# MCU.net
KiCad netlist of a schematic drawn in Altium Designer
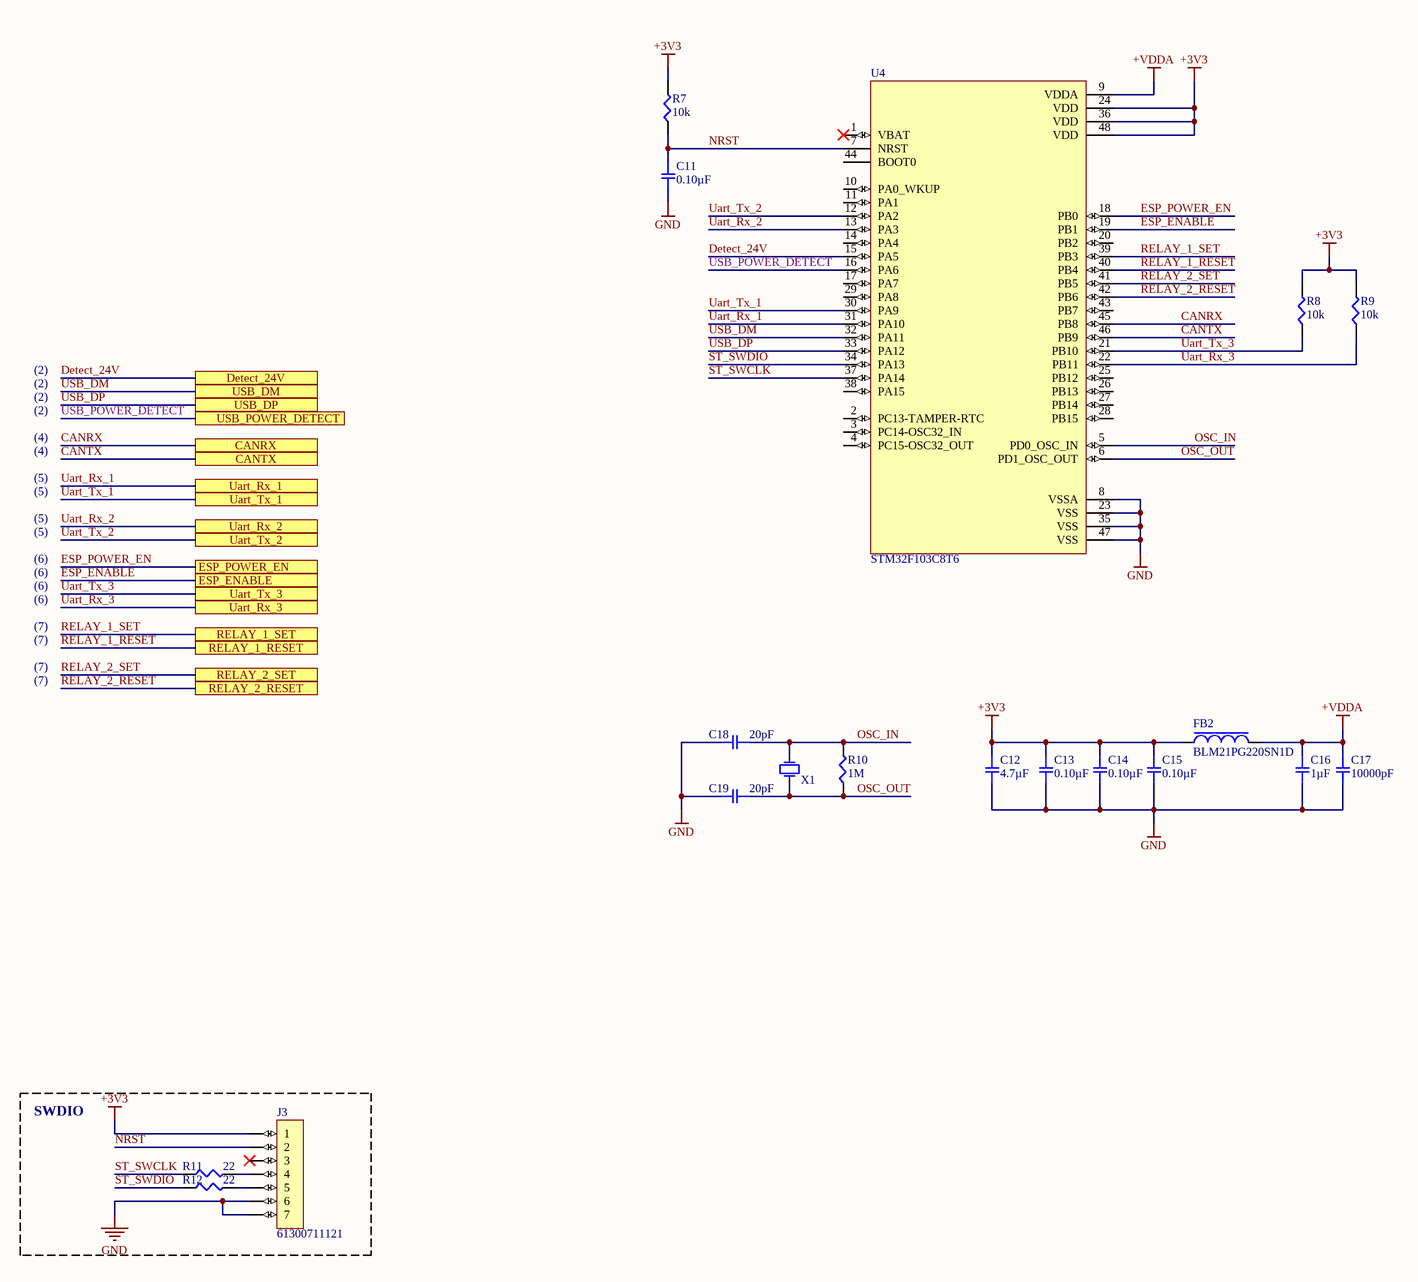
[diagram p0: MCU.SchDoc]

(export (version "E")
  (design (tool "Eeschema 10.0.6"))
  (components
    (comp (ref "C11")
      (value "0.10µF")
      (footprint "SMD-0603C")
      (description "CAP CER 0.1UF 50V X7R 0603")
      (fields
        (field (name "DIGI-KEY PART NUMBER") "490-5798-1-ND")
        (field (name "PART NUMBER") "GCJ188R71H104KA12D")
      )
      (libsource (lib "capacitor_murata_0603") (part "GCJ188R71H104KA12D"))
    )
    (comp (ref "C12")
      (value "4.7µF")
      (footprint "SMD-0805C")
      (description "CAP CER 4.7UF 16V X7R 0805")
      (fields
        (field (name "DIGI-KEY PART NUMBER") "490-10557-1-ND")
        (field (name "PART NUMBER") "GCJ21BR71C475KA01L")
      )
      (libsource (lib "capacitor_murata_0805") (part "GCJ21BR71C475KA01L"))
    )
    (comp (ref "C13")
      (value "0.10µF")
      (footprint "SMD-0603C")
      (description "CAP CER 0.1UF 50V X7R 0603")
      (fields
        (field (name "DIGI-KEY PART NUMBER") "490-5798-1-ND")
        (field (name "PART NUMBER") "GCJ188R71H104KA12D")
      )
      (libsource (lib "capacitor_murata_0603") (part "GCJ188R71H104KA12D"))
    )
    (comp (ref "C14")
      (value "0.10µF")
      (footprint "SMD-0603C")
      (description "CAP CER 0.1UF 50V X7R 0603")
      (fields
        (field (name "DIGI-KEY PART NUMBER") "490-5798-1-ND")
        (field (name "PART NUMBER") "GCJ188R71H104KA12D")
      )
      (libsource (lib "capacitor_murata_0603") (part "GCJ188R71H104KA12D"))
    )
    (comp (ref "C15")
      (value "0.10µF")
      (footprint "SMD-0603C")
      (description "CAP CER 0.1UF 50V X7R 0603")
      (fields
        (field (name "DIGI-KEY PART NUMBER") "490-5798-1-ND")
        (field (name "PART NUMBER") "GCJ188R71H104KA12D")
      )
      (libsource (lib "capacitor_murata_0603") (part "GCJ188R71H104KA12D"))
    )
    (comp (ref "C16")
      (value "1µF")
      (footprint "SMD-0603C")
      (description "CAP CER 1UF 16V X7R 0603")
      (fields
        (field (name "DIGI-KEY PART NUMBER") "490-5241-1-ND")
        (field (name "PART NUMBER") "GCM188R71C105KA64D")
      )
      (libsource (lib "capacitor_murata_0603") (part "GCM188R71C105KA64D"))
    )
    (comp (ref "C17")
      (value "10000pF")
      (footprint "SMD-0603C")
      (description "CAP CER 10000PF 16V X7R 0603")
      (fields
        (field (name "DIGI-KEY PART NUMBER") "490-1525-1-ND")
        (field (name "PART NUMBER") "GRM188R71C103KA01D")
      )
      (libsource (lib "capacitor_murata_0603") (part "GRM188R71C103KA01D"))
    )
    (comp (ref "C18")
      (value "20pF")
      (footprint "SMD-0603C")
      (description "CAP CER 20PF 50V NP0 0603")
      (fields
        (field (name "DIGI-KEY PART NUMBER") "490-13299-1-ND")
        (field (name "PART NUMBER") "GCM1885C1H200JA16D")
      )
      (libsource (lib "capacitor_murata_0603") (part "GCM1885C1H200JA16D"))
    )
    (comp (ref "C19")
      (value "20pF")
      (footprint "SMD-0603C")
      (description "CAP CER 20PF 50V NP0 0603")
      (fields
        (field (name "DIGI-KEY PART NUMBER") "490-13299-1-ND")
        (field (name "PART NUMBER") "GCM1885C1H200JA16D")
      )
      (libsource (lib "capacitor_murata_0603") (part "GCM1885C1H200JA16D"))
    )
    (comp (ref "FB2")
      (value "BLM21PG220SN1D")
      (footprint "L-0805")
      (description "FERRITE BEAD 22 OHM 0805 1LN")
      (fields (field (name "MANUFACTURER") "Murata") (field (name "TOLERANCE") "25%"))
      (libsource (lib "Altium_Lib") (part "Ferrite_Bead__BLM21PG220SN1D"))
    )
    (comp (ref "J3")
      (value "61300711121")
      (footprint "HEADER_7__61300711121")
      (description "CONN HEADER 7 POS 2.54")
      (fields (field (name "MANUFACTURER") "Wurth Electronics Inc."))
      (libsource (lib "Altium_Lib") (part "HEADER_7__61300711121"))
    )
    (comp (ref "R7")
      (value "10k")
      (footprint "SMD-0603-RES")
      (description "RES SMD 10K OHM 5% 1/10W 0603")
      (fields (field (name "PART NUMBER") "ERJ-3GEYJ103V") (field (name "DIGI-KEY PART NUMBER") "P10KGCT-ND"))
      (libsource (lib "Panasonic_ERJ_0603") (part "ERJ-3GEYJ103V"))
    )
    (comp (ref "R8")
      (value "10k")
      (footprint "SMD-0603-RES")
      (description "RES SMD 10K OHM 1% 1/10W 0603")
      (fields
        (field (name "PART NUMBER") "ERJ-3EKF1002V")
        (field (name "DIGI-KEY PART NUMBER") "P10.0KHCT-ND")
      )
      (libsource (lib "Panasonic_ERJ_0603") (part "ERJ-3EKF1002V"))
    )
    (comp (ref "R9")
      (value "10k")
      (footprint "SMD-0603-RES")
      (description "RES SMD 10K OHM 1% 1/10W 0603")
      (fields
        (field (name "PART NUMBER") "ERJ-3EKF1002V")
        (field (name "DIGI-KEY PART NUMBER") "P10.0KHCT-ND")
      )
      (libsource (lib "Panasonic_ERJ_0603") (part "ERJ-3EKF1002V"))
    )
    (comp (ref "R10")
      (value "1M")
      (footprint "SMD-0603-RES")
      (description "RES SMD 1M OHM 5% 1/10W 0603")
      (fields
        (field (name "PART NUMBER") "ERJ-3GEYJ105V")
        (field (name "DIGI-KEY PART NUMBER") "P1.0MGCT-ND")
      )
      (libsource (lib "Panasonic_ERJ_0603") (part "ERJ-3GEYJ105V"))
    )
    (comp (ref "R11")
      (value "22")
      (footprint "SMD-0603-RES")
      (description "RES SMD 22 OHM 1% 1/10W 0603")
      (fields
        (field (name "PART NUMBER") "ERJ-3EKF22R0V")
        (field (name "DIGI-KEY PART NUMBER") "P22.0HCT-ND")
      )
      (libsource (lib "Panasonic_ERJ_0603") (part "ERJ-3EKF22R0V"))
    )
    (comp (ref "R12")
      (value "22")
      (footprint "SMD-0603-RES")
      (description "RES SMD 22 OHM 1% 1/10W 0603")
      (fields
        (field (name "PART NUMBER") "ERJ-3EKF22R0V")
        (field (name "DIGI-KEY PART NUMBER") "P22.0HCT-ND")
      )
      (libsource (lib "Panasonic_ERJ_0603") (part "ERJ-3EKF22R0V"))
    )
    (comp (ref "U4")
      (value "STM32F103C8T6")
      (footprint "QFN48-(7mmX7mm)")
      (description "IC MCU 32-Bit 72MHz 64kB FLASH LQFP48")
      (fields (field (name "MF") "STMicroelectronics"))
      (libsource (lib "Altium_Lib") (part "STM32F103C8T6"))
    )
    (comp (ref "X1")
      (value "EB3250AYA08-8.000M TR")
      (footprint "XTAL_3.2mm_1.5mm_2pad")
      (description "Crystal 8MHz 8pF Automotive 2-Pin CSMD T/R")
      (fields (field (name "MANUFACTURER") "Ecliptek"))
      (libsource (lib "Altium_Lib") (part "CRYSTAL__ECS-.327-12.5-34B-TR"))
    )
  )
  (nets
    (net (code "1") (name "+3V3") (class "Default")
      (node (ref "C12") (pin "1") (pinfunction "1_1") (pintype "passive"))
      (node (ref "C13") (pin "1") (pinfunction "1_1") (pintype "passive"))
      (node (ref "C14") (pin "1") (pinfunction "1_1") (pintype "passive"))
      (node (ref "C15") (pin "1") (pinfunction "1_1") (pintype "passive"))
      (node (ref "FB2") (pin "1") (pinfunction "1_1") (pintype "passive"))
      (node (ref "J3") (pin "1") (pinfunction "1_1") (pintype "bidirectional"))
      (node (ref "R7") (pin "2") (pinfunction "2_2") (pintype "passive"))
      (node (ref "R8") (pin "2") (pinfunction "2_2") (pintype "passive"))
      (node (ref "R9") (pin "2") (pinfunction "2_2") (pintype "passive"))
      (node (ref "U4") (pin "24") (pinfunction "VDD_24") (pintype "passive"))
      (node (ref "U4") (pin "36") (pinfunction "VDD_36") (pintype "passive"))
      (node (ref "U4") (pin "48") (pinfunction "VDD_48") (pintype "passive"))
    )
    (net (code "2") (name "+VDDA") (class "Default")
      (node (ref "C16") (pin "1") (pinfunction "1_1") (pintype "passive"))
      (node (ref "C17") (pin "1") (pinfunction "1_1") (pintype "passive"))
      (node (ref "FB2") (pin "2") (pinfunction "2_2") (pintype "passive"))
      (node (ref "U4") (pin "9") (pinfunction "VDDA_9") (pintype "passive"))
    )
    (net (code "3") (name "/CANRX") (class "Default")
      (node (ref "U4") (pin "45") (pinfunction "PB8_45") (pintype "bidirectional"))
    )
    (net (code "4") (name "/CANTX") (class "Default")
      (node (ref "U4") (pin "46") (pinfunction "PB9_46") (pintype "bidirectional"))
    )
    (net (code "5") (name "/Detect_24V") (class "Default")
      (node (ref "U4") (pin "15") (pinfunction "PA5_15") (pintype "bidirectional"))
    )
    (net (code "6") (name "/ESP_ENABLE") (class "Default")
      (node (ref "U4") (pin "19") (pinfunction "PB1_19") (pintype "bidirectional"))
    )
    (net (code "7") (name "/ESP_POWER_EN") (class "Default")
      (node (ref "U4") (pin "18") (pinfunction "PB0_18") (pintype "bidirectional"))
    )
    (net (code "8") (name "/NRST") (class "Default")
      (node (ref "C11") (pin "1") (pinfunction "1_1") (pintype "passive"))
      (node (ref "J3") (pin "2") (pinfunction "2_2") (pintype "bidirectional"))
      (node (ref "R7") (pin "1") (pinfunction "1_1") (pintype "passive"))
      (node (ref "U4") (pin "7") (pinfunction "NRST_7") (pintype "passive"))
    )
    (net (code "9") (name "/OSC_IN") (class "Default")
      (node (ref "C18") (pin "1") (pinfunction "1_1") (pintype "passive"))
      (node (ref "R10") (pin "2") (pinfunction "2_2") (pintype "passive"))
      (node (ref "U4") (pin "5") (pinfunction "PD0_OSC_IN_5") (pintype "bidirectional"))
      (node (ref "X1") (pin "2") (pinfunction "OSC2_2") (pintype "passive"))
    )
    (net (code "10") (name "/OSC_OUT") (class "Default")
      (node (ref "C19") (pin "1") (pinfunction "1_1") (pintype "passive"))
      (node (ref "R10") (pin "1") (pinfunction "1_1") (pintype "passive"))
      (node (ref "U4") (pin "6") (pinfunction "PD1_OSC_OUT_6") (pintype "bidirectional"))
      (node (ref "X1") (pin "1") (pinfunction "OSC1_1") (pintype "passive"))
    )
    (net (code "11") (name "/RELAY_1_RESET") (class "Default")
      (node (ref "U4") (pin "40") (pinfunction "PB4_40") (pintype "bidirectional"))
    )
    (net (code "12") (name "/RELAY_1_SET") (class "Default")
      (node (ref "U4") (pin "39") (pinfunction "PB3_39") (pintype "bidirectional"))
    )
    (net (code "13") (name "/RELAY_2_RESET") (class "Default")
      (node (ref "U4") (pin "42") (pinfunction "PB6_42") (pintype "bidirectional"))
    )
    (net (code "14") (name "/RELAY_2_SET") (class "Default")
      (node (ref "U4") (pin "41") (pinfunction "PB5_41") (pintype "bidirectional"))
    )
    (net (code "15") (name "/ST_SWCLK") (class "Default")
      (node (ref "R11") (pin "1") (pinfunction "1_1") (pintype "passive"))
      (node (ref "U4") (pin "37") (pinfunction "PA14_37") (pintype "bidirectional"))
    )
    (net (code "16") (name "/ST_SWDIO") (class "Default")
      (node (ref "R12") (pin "1") (pinfunction "1_1") (pintype "passive"))
      (node (ref "U4") (pin "34") (pinfunction "PA13_34") (pintype "bidirectional"))
    )
    (net (code "17") (name "/USB_DM") (class "Default")
      (node (ref "U4") (pin "32") (pinfunction "PA11_32") (pintype "bidirectional"))
    )
    (net (code "18") (name "/USB_DP") (class "Default")
      (node (ref "U4") (pin "33") (pinfunction "PA12_33") (pintype "bidirectional"))
    )
    (net (code "19") (name "/USB_POWER_DETECT") (class "Default")
      (node (ref "U4") (pin "16") (pinfunction "PA6_16") (pintype "bidirectional"))
    )
    (net (code "20") (name "/Uart_Rx_1") (class "Default")
      (node (ref "U4") (pin "31") (pinfunction "PA10_31") (pintype "bidirectional"))
    )
    (net (code "21") (name "/Uart_Rx_2") (class "Default")
      (node (ref "U4") (pin "13") (pinfunction "PA3_13") (pintype "bidirectional"))
    )
    (net (code "22") (name "/Uart_Rx_3") (class "Default")
      (node (ref "R9") (pin "1") (pinfunction "1_1") (pintype "passive"))
      (node (ref "U4") (pin "22") (pinfunction "PB11_22") (pintype "bidirectional"))
    )
    (net (code "23") (name "/Uart_Tx_1") (class "Default")
      (node (ref "U4") (pin "30") (pinfunction "PA9_30") (pintype "bidirectional"))
    )
    (net (code "24") (name "/Uart_Tx_2") (class "Default")
      (node (ref "U4") (pin "12") (pinfunction "PA2_12") (pintype "bidirectional"))
    )
    (net (code "25") (name "/Uart_Tx_3") (class "Default")
      (node (ref "R8") (pin "1") (pinfunction "1_1") (pintype "passive"))
      (node (ref "U4") (pin "21") (pinfunction "PB10_21") (pintype "bidirectional"))
    )
    (net (code "26") (name "GND") (class "Default")
      (node (ref "C11") (pin "2") (pinfunction "2_2") (pintype "passive"))
      (node (ref "C12") (pin "2") (pinfunction "2_2") (pintype "passive"))
      (node (ref "C13") (pin "2") (pinfunction "2_2") (pintype "passive"))
      (node (ref "C14") (pin "2") (pinfunction "2_2") (pintype "passive"))
      (node (ref "C15") (pin "2") (pinfunction "2_2") (pintype "passive"))
      (node (ref "C16") (pin "2") (pinfunction "2_2") (pintype "passive"))
      (node (ref "C17") (pin "2") (pinfunction "2_2") (pintype "passive"))
      (node (ref "C18") (pin "2") (pinfunction "2_2") (pintype "passive"))
      (node (ref "C19") (pin "2") (pinfunction "2_2") (pintype "passive"))
      (node (ref "J3") (pin "6") (pinfunction "6_6") (pintype "bidirectional"))
      (node (ref "J3") (pin "7") (pinfunction "7_7") (pintype "bidirectional"))
      (node (ref "U4") (pin "23") (pinfunction "VSS_23") (pintype "passive"))
      (node (ref "U4") (pin "35") (pinfunction "VSS_35") (pintype "passive"))
      (node (ref "U4") (pin "47") (pinfunction "VSS_47") (pintype "passive"))
      (node (ref "U4") (pin "8") (pinfunction "VSSA_8") (pintype "passive"))
    )
    (net (code "27") (name "Net-(J3-Pad4)") (class "Default")
      (node (ref "J3") (pin "4") (pinfunction "4_4") (pintype "bidirectional"))
      (node (ref "R11") (pin "2") (pinfunction "2_2") (pintype "passive"))
    )
    (net (code "28") (name "Net-(J3-Pad5)") (class "Default")
      (node (ref "J3") (pin "5") (pinfunction "5_5") (pintype "bidirectional"))
      (node (ref "R12") (pin "2") (pinfunction "2_2") (pintype "passive"))
    )
    (net (code "29") (name "unconnected-(J3-Pad3)") (class "Default")
      (node (ref "J3") (pin "3") (pinfunction "3_3") (pintype "bidirectional+no_connect"))
    )
    (net (code "30") (name "unconnected-(U4-BOOT0-Pad44)") (class "Default")
      (node (ref "U4") (pin "44") (pinfunction "BOOT0_44") (pintype "passive"))
    )
    (net (code "31") (name "unconnected-(U4-PA0_WKUP-Pad10)") (class "Default")
      (node (ref "U4") (pin "10") (pinfunction "PA0_WKUP_10") (pintype "bidirectional"))
    )
    (net (code "32") (name "unconnected-(U4-PA1-Pad11)") (class "Default")
      (node (ref "U4") (pin "11") (pinfunction "PA1_11") (pintype "bidirectional"))
    )
    (net (code "33") (name "unconnected-(U4-PA4-Pad14)") (class "Default")
      (node (ref "U4") (pin "14") (pinfunction "PA4_14") (pintype "bidirectional"))
    )
    (net (code "34") (name "unconnected-(U4-PA7-Pad17)") (class "Default")
      (node (ref "U4") (pin "17") (pinfunction "PA7_17") (pintype "bidirectional"))
    )
    (net (code "35") (name "unconnected-(U4-PA8-Pad29)") (class "Default")
      (node (ref "U4") (pin "29") (pinfunction "PA8_29") (pintype "bidirectional"))
    )
    (net (code "36") (name "unconnected-(U4-PA15-Pad38)") (class "Default")
      (node (ref "U4") (pin "38") (pinfunction "PA15_38") (pintype "bidirectional"))
    )
    (net (code "37") (name "unconnected-(U4-PB2-Pad20)") (class "Default")
      (node (ref "U4") (pin "20") (pinfunction "PB2_20") (pintype "bidirectional"))
    )
    (net (code "38") (name "unconnected-(U4-PB7-Pad43)") (class "Default")
      (node (ref "U4") (pin "43") (pinfunction "PB7_43") (pintype "bidirectional"))
    )
    (net (code "39") (name "unconnected-(U4-PB12-Pad25)") (class "Default")
      (node (ref "U4") (pin "25") (pinfunction "PB12_25") (pintype "bidirectional"))
    )
    (net (code "40") (name "unconnected-(U4-PB13-Pad26)") (class "Default")
      (node (ref "U4") (pin "26") (pinfunction "PB13_26") (pintype "bidirectional"))
    )
    (net (code "41") (name "unconnected-(U4-PB14-Pad27)") (class "Default")
      (node (ref "U4") (pin "27") (pinfunction "PB14_27") (pintype "bidirectional"))
    )
    (net (code "42") (name "unconnected-(U4-PB15-Pad28)") (class "Default")
      (node (ref "U4") (pin "28") (pinfunction "PB15_28") (pintype "bidirectional"))
    )
    (net (code "43") (name "unconnected-(U4-PC13-TAMPER-RTC-Pad2)") (class "Default")
      (node (ref "U4") (pin "2") (pinfunction "PC13-TAMPER-RTC_2") (pintype "bidirectional"))
    )
    (net (code "44") (name "unconnected-(U4-PC14-OSC32_IN-Pad3)") (class "Default")
      (node (ref "U4") (pin "3") (pinfunction "PC14-OSC32_IN_3") (pintype "bidirectional"))
    )
    (net (code "45") (name "unconnected-(U4-PC15-OSC32_OUT-Pad4)") (class "Default")
      (node (ref "U4") (pin "4") (pinfunction "PC15-OSC32_OUT_4") (pintype "bidirectional"))
    )
    (net (code "46") (name "unconnected-(U4-VBAT-Pad1)") (class "Default")
      (node (ref "U4") (pin "1") (pinfunction "VBAT_1") (pintype "bidirectional+no_connect"))
    )
  )
)
